# CSMS.net
KiCad netlist of a schematic drawn in Altium Designer
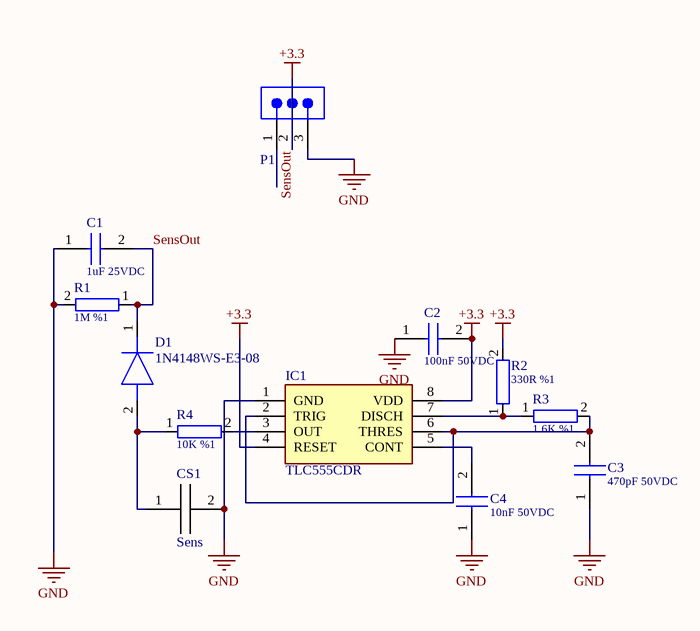
[diagram p0: CSMS.SchDoc]

(export (version "E")
  (design (tool "Eeschema 10.0.6"))
  (components
    (comp (ref "C1")
      (value "1uF 25VDC")
      (footprint "0603 CAP")
      (description "1uF 25VDC ±10% X7R MLCC 0603")
      (fields (field (name "Comment") "CL10B105KA8NNNC"))
      (libsource (lib "CSMS") (part "CL10B105KA8NNNC"))
    )
    (comp (ref "C2")
      (value "100nF 50VDC")
      (footprint "0603 CAP")
      (description "100nF 50VDC ±10% X7R MLCC 0603")
      (fields (field (name "Comment") "CL10B104KB8NNNC"))
      (libsource (lib "CSMS") (part "CL10B104KB8NNNC"))
    )
    (comp (ref "C3")
      (value "470pF 50VDC")
      (footprint "0603 CAP")
      (description "470pF 50VDC ±10% X7R MLCC 0603")
      (fields (field (name "Comment") "CL10B471KB8NNNC"))
      (libsource (lib "CSMS") (part "CL10B471KB8NNNC"))
    )
    (comp (ref "C4")
      (value "10nF 50VDC")
      (footprint "0603 CAP")
      (description "10nF, 50 V, ± 10%, X7R, 0603, Multilayer Ceramic Capacitor,")
      (fields (field (name "Comment") "CC0603KRX7R9BB103"))
      (libsource (lib "CSMS") (part "CC0603KRX7R9BB103"))
    )
    (comp (ref "CS1")
      (value "Sens")
      (footprint "Sens")
      (description "Pcb Sens")
      (libsource (lib "CSMS") (part "Sens"))
    )
    (comp (ref "D1")
      (value "1N4148WS-E3-08")
      (footprint "SOD2513X110N")
      (description "Diode")
      (fields (field (name "MOUSER PART NUMBER") "78-1N4148WS-E3-08"))
      (libsource (lib "CSMS") (part "1N4148WS-E3-08"))
    )
    (comp (ref "IC1")
      (value "TLC555CDR")
      (footprint "SOIC127P600X175-8N")
      (description "555 Astable 2.1-MHz, 250-µA, Low-Power Timer 8-SOIC 0 to 70")
      (fields (field (name "MOUSER PART NUMBER") "595-TLC555CDR"))
      (libsource (lib "CSMS") (part "TLC555CDR"))
    )
    (comp (ref "P1")
      (value "61300311021")
      (footprint "61300311021")
      (description "WR-PHD Pin Header, THT, Angled, pitch 2.54mm, 1 Row, 3P")
      (fields (field (name "MANUFACTURER") "Wurth Elektronik"))
      (libsource (lib "CSMS") (part "61300311021"))
    )
    (comp (ref "R1")
      (value "1M %1")
      (footprint "0603 RES")
      (description "1M Ohms 1% 1/10W-S 100PPM RES 0603")
      (fields (field (name "Comment") "0603SAF1004T5E"))
      (libsource (lib "CSMS") (part "0603SAF1004T5E"))
    )
    (comp (ref "R2")
      (value "330R %1")
      (footprint "0603 RES")
      (description "330R Ohms 1% 1/10W-S 100PPM RES 0603")
      (fields (field (name "Comment") "0603SAF3300T5E"))
      (libsource (lib "CSMS") (part "0603SAF3300T5E"))
    )
    (comp (ref "R3")
      (value "1.6K %1")
      (footprint "0603 RES")
      (description "1.6K Ohms 1% 1/10W-S 100PPM RES 0603")
      (fields (field (name "Comment") "0603SAF1601T5E"))
      (libsource (lib "CSMS") (part "0603SAF1601T5E"))
    )
    (comp (ref "R4")
      (value "10K %1")
      (footprint "0603 RES")
      (description "10K Ohms 1% 1/10W-S 100PPM RES 0603")
      (fields (field (name "Comment") "0603SAF1002T5E"))
      (libsource (lib "CSMS") (part "0603SAF1002T5E"))
    )
  )
  (nets
    (net (code "1") (name "+3.3") (class "Default")
      (node (ref "C2") (pin "2") (pinfunction "2_2") (pintype "passive"))
      (node (ref "IC1") (pin "4") (pinfunction "RESET_4") (pintype "passive"))
      (node (ref "IC1") (pin "8") (pinfunction "VDD_8") (pintype "passive"))
      (node (ref "P1") (pin "2") (pinfunction "2_2") (pintype "passive"))
      (node (ref "R2") (pin "2") (pinfunction "2_2") (pintype "passive"))
    )
    (net (code "2") (name "/SensOut") (class "Default")
      (node (ref "C1") (pin "2") (pinfunction "2_2") (pintype "passive"))
      (node (ref "D1") (pin "1") (pinfunction "K_1") (pintype "passive"))
      (node (ref "P1") (pin "1") (pinfunction "1_1") (pintype "passive"))
      (node (ref "R1") (pin "1") (pinfunction "1_1") (pintype "passive"))
    )
    (net (code "3") (name "GND") (class "Default")
      (node (ref "C1") (pin "1") (pinfunction "1_1") (pintype "passive"))
      (node (ref "C2") (pin "1") (pinfunction "1_1") (pintype "passive"))
      (node (ref "C3") (pin "1") (pinfunction "1_1") (pintype "passive"))
      (node (ref "C4") (pin "1") (pinfunction "1_1") (pintype "passive"))
      (node (ref "CS1") (pin "2") (pinfunction "2_2") (pintype "passive"))
      (node (ref "IC1") (pin "1") (pinfunction "GND_1") (pintype "passive"))
      (node (ref "P1") (pin "3") (pinfunction "3_3") (pintype "passive"))
      (node (ref "R1") (pin "2") (pinfunction "2_2") (pintype "passive"))
    )
    (net (code "4") (name "Net-(D1-A)") (class "Default")
      (node (ref "CS1") (pin "1") (pinfunction "1_1") (pintype "passive"))
      (node (ref "D1") (pin "2") (pinfunction "A_2") (pintype "passive"))
      (node (ref "R4") (pin "1") (pinfunction "1_1") (pintype "passive"))
    )
    (net (code "5") (name "Net-(IC1-CONT)") (class "Default")
      (node (ref "C4") (pin "2") (pinfunction "2_2") (pintype "passive"))
      (node (ref "IC1") (pin "5") (pinfunction "CONT_5") (pintype "passive"))
    )
    (net (code "6") (name "Net-(IC1-DISCH)") (class "Default")
      (node (ref "IC1") (pin "7") (pinfunction "DISCH_7") (pintype "passive"))
      (node (ref "R2") (pin "1") (pinfunction "1_1") (pintype "passive"))
      (node (ref "R3") (pin "1") (pinfunction "1_1") (pintype "passive"))
    )
    (net (code "7") (name "Net-(IC1-OUT)") (class "Default")
      (node (ref "IC1") (pin "3") (pinfunction "OUT_3") (pintype "passive"))
      (node (ref "R4") (pin "2") (pinfunction "2_2") (pintype "passive"))
    )
    (net (code "8") (name "Net-(IC1-THRES)") (class "Default")
      (node (ref "C3") (pin "2") (pinfunction "2_2") (pintype "passive"))
      (node (ref "IC1") (pin "2") (pinfunction "TRIG_2") (pintype "passive"))
      (node (ref "IC1") (pin "6") (pinfunction "THRES_6") (pintype "passive"))
      (node (ref "R3") (pin "2") (pinfunction "2_2") (pintype "passive"))
    )
  )
)
